# BodyCaINseedv0_2.net
KiCad netlist of a schematic drawn in Altium Designer
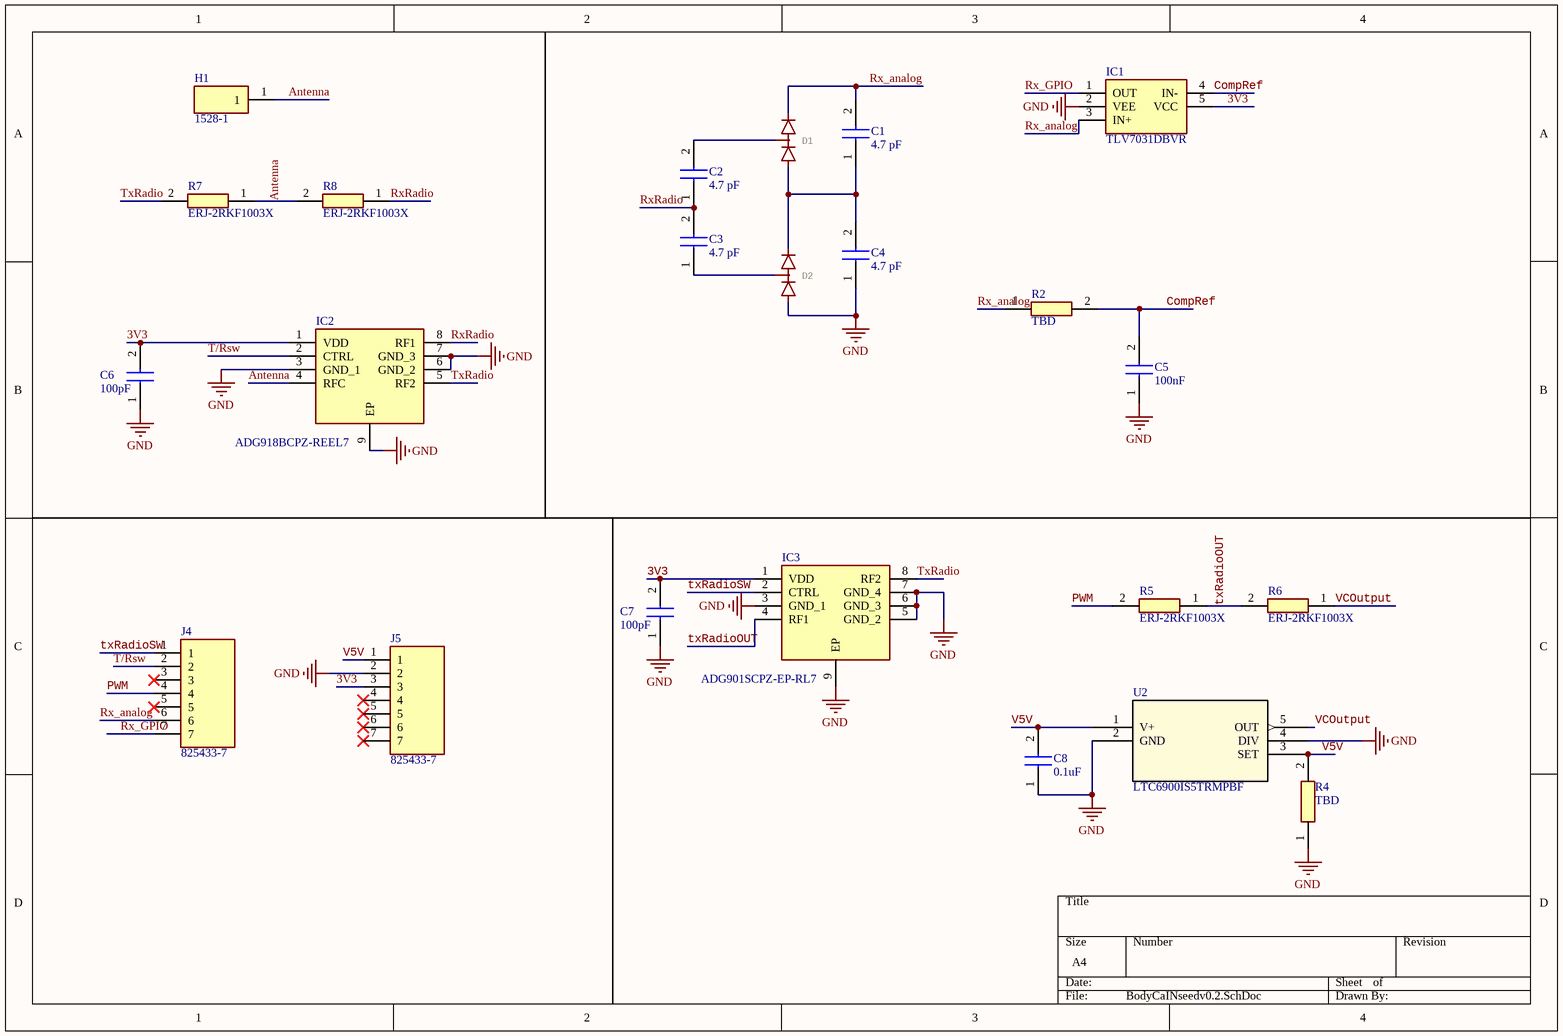
[diagram p0: BodyCaINseedv0.2.SchDoc]

(export (version "E")
  (design (tool "Eeschema 10.0.6"))
  (components
    (comp (ref "C1")
      (value "4.7 pF")
      (footprint "CAPC1608X73N")
      (description "Capacitor 06035J4R7BBSTR")
      (fields
        (field (name "MANUFACTURER_PART_NUMBER") "06035J4R7BBSTR")
        (field (name "MOUSER PART NUMBER") "581-06035J4R7BBS")
      )
      (libsource (lib "BodyCaINv0.1") (part "06035J4R7BBSTR"))
    )
    (comp (ref "C2")
      (value "4.7 pF")
      (footprint "CAPC1608X73N")
      (description "Capacitor 06035J4R7BBSTR")
      (fields
        (field (name "MANUFACTURER_PART_NUMBER") "06035J4R7BBSTR")
        (field (name "MOUSER PART NUMBER") "581-06035J4R7BBS")
      )
      (libsource (lib "BodyCaINv0.1") (part "06035J4R7BBSTR"))
    )
    (comp (ref "C3")
      (value "4.7 pF")
      (footprint "CAPC1608X73N")
      (description "Capacitor 06035J4R7BBSTR")
      (fields
        (field (name "MANUFACTURER_PART_NUMBER") "06035J4R7BBSTR")
        (field (name "MOUSER PART NUMBER") "581-06035J4R7BBS")
      )
      (libsource (lib "BodyCaINv0.1") (part "06035J4R7BBSTR"))
    )
    (comp (ref "C4")
      (value "4.7 pF")
      (footprint "CAPC1608X73N")
      (description "Capacitor 06035J4R7BBSTR")
      (fields
        (field (name "MANUFACTURER_PART_NUMBER") "06035J4R7BBSTR")
        (field (name "MOUSER PART NUMBER") "581-06035J4R7BBS")
      )
      (libsource (lib "BodyCaINv0.1") (part "06035J4R7BBSTR"))
    )
    (comp (ref "C5")
      (value "100nF")
      (footprint "CAPC1608X90N")
      (description "Capacitor GCM188R71H103KA37J")
      (fields
        (field (name "MANUFACTURER_PART_NUMBER") "GCM188R71H103KA37J")
        (field (name "MOUSER PART NUMBER") "81-GCM188R71H103KA7J")
      )
      (libsource (lib "BodyCaINv0.1") (part "GCM188R71H103KA37J"))
    )
    (comp (ref "C6")
      (value "100pF")
      (footprint "CAPC1608X97N")
      (description "Capacitor VJ0603A101FXAAC")
      (fields
        (field (name "MANUFACTURER_PART_NUMBER") "VJ0603A101FXAAC")
        (field (name "MOUSER PART NUMBER") "77-VJ0603A101FXAAC")
      )
      (libsource (lib "BodyCaINv0.1") (part "VJ0603A101FXAAC"))
    )
    (comp (ref "C7")
      (value "100pF")
      (footprint "CAPC1608X97N")
      (description "Capacitor VJ0603A101FXAAC")
      (fields
        (field (name "MANUFACTURER_PART_NUMBER") "VJ0603A101FXAAC")
        (field (name "MOUSER PART NUMBER") "77-VJ0603A101FXAAC")
      )
      (libsource (lib "BodyCaINv0.1") (part "VJ0603A101FXAAC"))
    )
    (comp (ref "C8")
      (value "0.1uF")
      (footprint "CAPC1608X100N")
      (description "CapacitorC0603X104K1RACTU")
      (fields (field (name "MANUFACTURER_PART_NUMBER") "C0603X104K1RACTU"))
      (libsource (lib "BodyCaINv0.1") (part "C0603X104K1RACTU"))
    )
    (comp (ref "D1")
      (value "RB706F-40FHT106")
      (footprint "SOT23")
      (description "2 Diodes - Cathode-Anode¦Cathode-Anode DIODE_2CACA-SOT23")
      (libsource (lib "CaINv3.02") (part "DIODE_2CACA-SOT23"))
    )
    (comp (ref "D2")
      (value "RB706F-40FHT106")
      (footprint "SOT23")
      (description "2 Diodes - Cathode-Anode¦Cathode-Anode DIODE_2CACA-SOT23")
      (libsource (lib "CaINv3.02") (part "DIODE_2CACA-SOT23"))
    )
    (comp (ref "H1")
      (value "1528-1")
      (footprint "SamacSys:15281")
      (description "Hardware")
      (fields (field (name "MOUSER PART NUMBER") "534-1528-1"))
      (libsource (lib "SamacSys") (part "1528-1"))
    )
    (comp (ref "IC1")
      (value "TLV7031DBVR")
      (footprint "SOT95P280X145-5N")
      (description "Integrated Circuit")
      (fields (field (name "MOUSER PART NUMBER") "595-TLV7031DBVR"))
      (libsource (lib "BodyCaINv0.1") (part "TLV7031DBVR"))
    )
    (comp (ref "IC2")
      (value "ADG918BCPZ-REEL7")
      (footprint "SamacSys:SON50P300X300X85-9N-D")
      (description "Integrated Circuit")
      (fields (field (name "MOUSER PART NUMBER") "584-ADG918BCPZ-R7"))
      (libsource (lib "*") (part "ADG918BCPZ-REEL7"))
    )
    (comp (ref "IC3")
      (value "ADG901SCPZ-EP-RL7")
      (footprint "SamacSys:SON50P300X300X85-9N-D")
      (description "Integrated Circuit")
      (fields (field (name "MOUSER PART NUMBER") "584-ADG901SCPZEPRL7"))
      (libsource (lib "*") (part "ADG901SCPZ-EP-RL7"))
    )
    (comp (ref "J4")
      (value "825433-7")
      (footprint "1725708")
      (description "Connector")
      (fields (field (name "MOUSER PART NUMBER") "571-825433-7"))
      (libsource (lib "*") (part "825433-7"))
    )
    (comp (ref "J5")
      (value "825433-7")
      (footprint "1725708")
      (description "Connector")
      (fields (field (name "MOUSER PART NUMBER") "571-825433-7"))
      (libsource (lib "*") (part "825433-7"))
    )
    (comp (ref "R2")
      (value "TBD")
      (footprint "RESC1508X46N")
      (description "Resistor WSL060300000ZEA9")
      (fields
        (field (name "MANUFACTURER_PART_NUMBER") "WSL060300000ZEA9")
        (field (name "MOUSER PART NUMBER") "71-WSL060300000ZEA9")
      )
      (libsource (lib "BodyCaINv0.1") (part "WSL060300000ZEA9"))
    )
    (comp (ref "R4")
      (value "TBD")
      (footprint "RESC1508X46N")
      (description "Resistor WSL060300000ZEA9")
      (fields
        (field (name "MANUFACTURER_PART_NUMBER") "WSL060300000ZEA9")
        (field (name "MOUSER PART NUMBER") "71-WSL060300000ZEA9")
      )
      (libsource (lib "") (part "WSL060300000ZEA9_1"))
    )
    (comp (ref "R5")
      (value "ERJ-2RKF1003X")
      (footprint "SamacSys:ERJ2RKD1004X")
      (description "Resistor")
      (fields (field (name "MOUSER PART NUMBER") "667-ERJ-2RKF1003X"))
      (libsource (lib "*") (part "ERJ-2RKF1003X"))
    )
    (comp (ref "R6")
      (value "ERJ-2RKF1003X")
      (footprint "SamacSys:ERJ2RKD1004X")
      (description "Resistor")
      (fields (field (name "MOUSER PART NUMBER") "667-ERJ-2RKF1003X"))
      (libsource (lib "*") (part "ERJ-2RKF1003X"))
    )
    (comp (ref "R7")
      (value "ERJ-2RKF1003X")
      (footprint "SamacSys:ERJ2RKD1004X")
      (description "Resistor")
      (fields (field (name "MOUSER PART NUMBER") "667-ERJ-2RKF1003X"))
      (libsource (lib "*") (part "ERJ-2RKF1003X"))
    )
    (comp (ref "R8")
      (value "ERJ-2RKF1003X")
      (footprint "SamacSys:ERJ2RKD1004X")
      (description "Resistor")
      (fields (field (name "MOUSER PART NUMBER") "667-ERJ-2RKF1003X"))
      (libsource (lib "*") (part "ERJ-2RKF1003X"))
    )
    (comp (ref "U2")
      (value "LTC6900IS5TRMPBF")
      (footprint "S_5_ADI")
      (description "No Description Available")
      (libsource (lib "BodyCaINv0.1") (part "LTC6900IS5TRMPBF"))
    )
  )
  (nets
    (net (code "1") (name "/3V3") (class "Default")
      (node (ref "C6") (pin "2") (pinfunction "2_2") (pintype "passive"))
      (node (ref "C7") (pin "2") (pinfunction "2_2") (pintype "passive"))
      (node (ref "IC1") (pin "5") (pinfunction "VCC_5") (pintype "passive"))
      (node (ref "IC2") (pin "1") (pinfunction "VDD_1") (pintype "passive"))
      (node (ref "IC3") (pin "1") (pinfunction "VDD_1") (pintype "passive"))
      (node (ref "J5") (pin "3") (pinfunction "3_3") (pintype "passive"))
    )
    (net (code "2") (name "/Antenna") (class "Default")
      (node (ref "H1") (pin "1") (pinfunction "1_1") (pintype "passive"))
      (node (ref "IC2") (pin "4") (pinfunction "RFC_4") (pintype "passive"))
      (node (ref "R7") (pin "1") (pinfunction "1_1") (pintype "passive"))
      (node (ref "R8") (pin "2") (pinfunction "2_2") (pintype "passive"))
    )
    (net (code "3") (name "/CompRef") (class "Default")
      (node (ref "C5") (pin "2") (pinfunction "2_2") (pintype "passive"))
      (node (ref "IC1") (pin "4") (pinfunction "IN-_4") (pintype "passive"))
      (node (ref "R2") (pin "2") (pinfunction "2_2") (pintype "passive"))
    )
    (net (code "4") (name "/PWM") (class "Default")
      (node (ref "J4") (pin "4") (pinfunction "4_4") (pintype "passive"))
      (node (ref "R5") (pin "2") (pinfunction "2_2") (pintype "passive"))
    )
    (net (code "5") (name "/RxRadio") (class "Default")
      (node (ref "C2") (pin "1") (pinfunction "1_1") (pintype "passive"))
      (node (ref "C3") (pin "2") (pinfunction "2_2") (pintype "passive"))
      (node (ref "IC2") (pin "8") (pinfunction "RF1_8") (pintype "passive"))
      (node (ref "R8") (pin "1") (pinfunction "1_1") (pintype "passive"))
    )
    (net (code "6") (name "/Rx_GPIO") (class "Default")
      (node (ref "IC1") (pin "1") (pinfunction "OUT_1") (pintype "passive"))
      (node (ref "J4") (pin "7") (pinfunction "7_7") (pintype "passive"))
    )
    (net (code "7") (name "/Rx_analog") (class "Default")
      (node (ref "C1") (pin "2") (pinfunction "2_2") (pintype "passive"))
      (node (ref "D1") (pin "2") (pinfunction "C_2") (pintype "passive"))
      (node (ref "IC1") (pin "3") (pinfunction "IN+_3") (pintype "passive"))
      (node (ref "J4") (pin "6") (pinfunction "6_6") (pintype "passive"))
      (node (ref "R2") (pin "1") (pinfunction "1_1") (pintype "passive"))
    )
    (net (code "8") (name "/TxRadio") (class "Default")
      (node (ref "IC2") (pin "5") (pinfunction "RF2_5") (pintype "passive"))
      (node (ref "IC3") (pin "8") (pinfunction "RF2_8") (pintype "passive"))
      (node (ref "R7") (pin "2") (pinfunction "2_2") (pintype "passive"))
    )
    (net (code "9") (name "/T{slash}Rsw") (class "Default")
      (node (ref "IC2") (pin "2") (pinfunction "CTRL_2") (pintype "passive"))
      (node (ref "J4") (pin "2") (pinfunction "2_2") (pintype "passive"))
    )
    (net (code "10") (name "/V5V") (class "Default")
      (node (ref "C8") (pin "2") (pinfunction "2_2") (pintype "passive"))
      (node (ref "J5") (pin "1") (pinfunction "1_1") (pintype "passive"))
      (node (ref "R4") (pin "2") (pinfunction "2_2") (pintype "passive"))
      (node (ref "U2") (pin "1") (pinfunction "V+_1") (pintype "passive"))
      (node (ref "U2") (pin "3") (pinfunction "SET_3") (pintype "passive"))
    )
    (net (code "11") (name "/VCOutput") (class "Default")
      (node (ref "R6") (pin "1") (pinfunction "1_1") (pintype "passive"))
      (node (ref "U2") (pin "5") (pinfunction "OUT_5") (pintype "output"))
    )
    (net (code "12") (name "/txRadioOUT") (class "Default")
      (node (ref "IC3") (pin "4") (pinfunction "RF1_4") (pintype "passive"))
      (node (ref "R5") (pin "1") (pinfunction "1_1") (pintype "passive"))
      (node (ref "R6") (pin "2") (pinfunction "2_2") (pintype "passive"))
    )
    (net (code "13") (name "/txRadioSW") (class "Default")
      (node (ref "IC3") (pin "2") (pinfunction "CTRL_2") (pintype "passive"))
      (node (ref "J4") (pin "1") (pinfunction "1_1") (pintype "passive"))
    )
    (net (code "14") (name "GND") (class "Default")
      (node (ref "C4") (pin "1") (pinfunction "1_1") (pintype "passive"))
      (node (ref "C5") (pin "1") (pinfunction "1_1") (pintype "passive"))
      (node (ref "C6") (pin "1") (pinfunction "1_1") (pintype "passive"))
      (node (ref "C7") (pin "1") (pinfunction "1_1") (pintype "passive"))
      (node (ref "C8") (pin "1") (pinfunction "1_1") (pintype "passive"))
      (node (ref "D2") (pin "1") (pinfunction "A_1") (pintype "passive"))
      (node (ref "IC1") (pin "2") (pinfunction "VEE_2") (pintype "passive"))
      (node (ref "IC2") (pin "3") (pinfunction "GND_1_3") (pintype "passive"))
      (node (ref "IC2") (pin "6") (pinfunction "GND_2_6") (pintype "passive"))
      (node (ref "IC2") (pin "7") (pinfunction "GND_3_7") (pintype "passive"))
      (node (ref "IC2") (pin "9") (pinfunction "EP_9") (pintype "passive"))
      (node (ref "IC3") (pin "3") (pinfunction "GND_1_3") (pintype "passive"))
      (node (ref "IC3") (pin "5") (pinfunction "GND_2_5") (pintype "passive"))
      (node (ref "IC3") (pin "6") (pinfunction "GND_3_6") (pintype "passive"))
      (node (ref "IC3") (pin "7") (pinfunction "GND_4_7") (pintype "passive"))
      (node (ref "IC3") (pin "9") (pinfunction "EP_9") (pintype "passive"))
      (node (ref "J5") (pin "2") (pinfunction "2_2") (pintype "passive"))
      (node (ref "R4") (pin "1") (pinfunction "1_1") (pintype "passive"))
      (node (ref "U2") (pin "2") (pinfunction "GND_2") (pintype "power_in"))
      (node (ref "U2") (pin "4") (pinfunction "DIV_4") (pintype "passive"))
    )
    (net (code "15") (name "Net-(D1-A)") (class "Default")
      (node (ref "C1") (pin "1") (pinfunction "1_1") (pintype "passive"))
      (node (ref "C4") (pin "2") (pinfunction "2_2") (pintype "passive"))
      (node (ref "D1") (pin "1") (pinfunction "A_1") (pintype "passive"))
      (node (ref "D2") (pin "2") (pinfunction "C_2") (pintype "passive"))
    )
    (net (code "16") (name "Net-(D1-AC)") (class "Default")
      (node (ref "C2") (pin "2") (pinfunction "2_2") (pintype "passive"))
      (node (ref "D1") (pin "3") (pinfunction "AC_3") (pintype "passive"))
    )
    (net (code "17") (name "Net-(D2-AC)") (class "Default")
      (node (ref "C3") (pin "1") (pinfunction "1_1") (pintype "passive"))
      (node (ref "D2") (pin "3") (pinfunction "AC_3") (pintype "passive"))
    )
    (net (code "18") (name "unconnected-(J4-Pad3)") (class "Default")
      (node (ref "J4") (pin "3") (pinfunction "3_3") (pintype "passive+no_connect"))
    )
    (net (code "19") (name "unconnected-(J4-Pad5)") (class "Default")
      (node (ref "J4") (pin "5") (pinfunction "5_5") (pintype "passive+no_connect"))
    )
    (net (code "20") (name "unconnected-(J5-Pad4)") (class "Default")
      (node (ref "J5") (pin "4") (pinfunction "4_4") (pintype "passive+no_connect"))
    )
    (net (code "21") (name "unconnected-(J5-Pad5)") (class "Default")
      (node (ref "J5") (pin "5") (pinfunction "5_5") (pintype "passive+no_connect"))
    )
    (net (code "22") (name "unconnected-(J5-Pad6)") (class "Default")
      (node (ref "J5") (pin "6") (pinfunction "6_6") (pintype "passive+no_connect"))
    )
    (net (code "23") (name "unconnected-(J5-Pad7)") (class "Default")
      (node (ref "J5") (pin "7") (pinfunction "7_7") (pintype "passive+no_connect"))
    )
  )
)
